# CurrentSense.net
KiCad netlist of a schematic drawn in Altium Designer
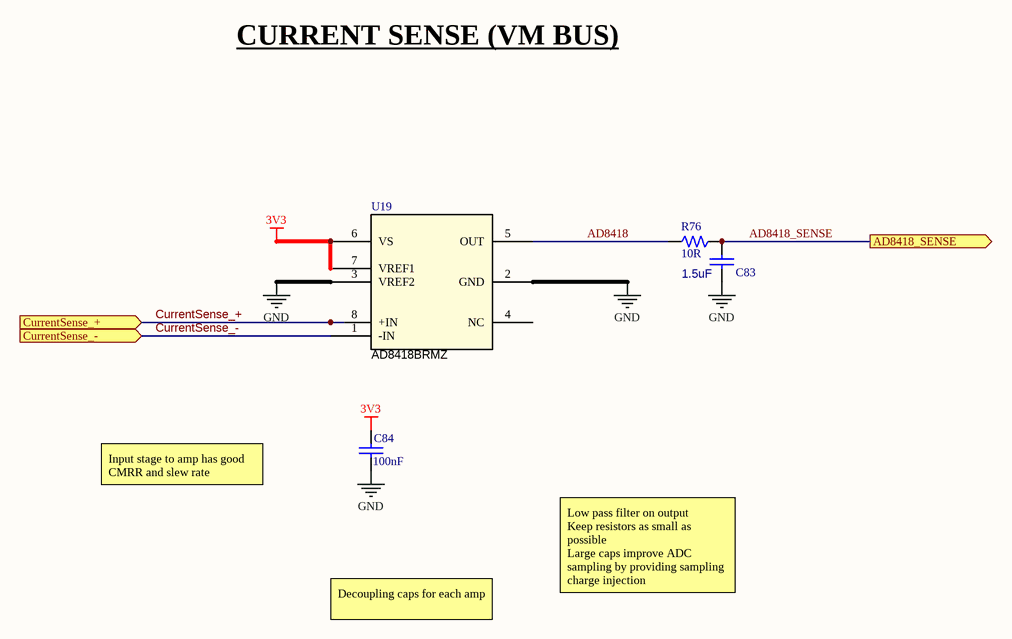
[diagram p0: CurrentSense.SchDoc]

(export (version "E")
  (design (tool "Eeschema 10.0.6"))
  (components
    (comp (ref "C83")
      (value "Capacitor")
      (footprint "CAP0402")
      (description "CAP CER 1.5UF 35V X5R 0402")
      (fields (field (name "CAPACITANCE") "1.5uF"))
      (libsource (lib "") (part "Capacitor_1"))
    )
    (comp (ref "C84")
      (value "Capacitor")
      (footprint "CAP0402")
      (fields
        (field (name "MANUFACTURER") "TDK")
        (field (name "MANUFACTURER PART NUMBER") "CGA2B3X7R1H104K050BB")
        (field (name "CAPACITANCE") "100nF")
        (field (name "TOLERANCE") "10%")
      )
      (libsource (lib "BPL-ShematicLibrary") (part "Capacitor"))
    )
    (comp (ref "R76")
      (value "Resistor")
      (footprint "RES0402")
      (fields (field (name "RESISTANCE") "10R") (field (name "TOLERANCE") "1%"))
      (libsource (lib "BPL-ShematicLibrary") (part "Resistor"))
    )
    (comp (ref "U19")
      (value "Current Sense")
      (footprint "AD8418BRMZ")
      (description "Current Sense Amplifier")
      (fields
        (field (name "MANUFACTURER") "Analog Devices Inc")
        (field (name "MANUFACTURER PART NUMBER") "AD8418BRMZ")
      )
      (libsource (lib "BPL-ShematicLibrary") (part "AD8418BRMZ"))
    )
  )
  (nets
    (net (code "1") (name "/AD8418") (class "Default")
      (node (ref "R76") (pin "2") (pinfunction "2_2") (pintype "passive"))
      (node (ref "U19") (pin "5") (pinfunction "OUT_5") (pintype "passive"))
    )
    (net (code "2") (name "/AD8418_SENSE") (class "Default")
      (node (ref "C83") (pin "1") (pinfunction "1_1") (pintype "passive"))
      (node (ref "R76") (pin "1") (pinfunction "1_1") (pintype "passive"))
    )
    (net (code "3") (name "/CurrentSense_+") (class "Default")
      (node (ref "U19") (pin "8") (pinfunction "+IN_8") (pintype "passive"))
    )
    (net (code "4") (name "/CurrentSense_-") (class "Default")
      (node (ref "U19") (pin "1") (pinfunction "-IN_1") (pintype "passive"))
    )
    (net (code "5") (name "3V3") (class "Default")
      (node (ref "C84") (pin "1") (pinfunction "1_1") (pintype "passive"))
      (node (ref "U19") (pin "6") (pinfunction "VS_6") (pintype "passive"))
      (node (ref "U19") (pin "7") (pinfunction "VREF1_7") (pintype "passive"))
    )
    (net (code "6") (name "GND") (class "Default")
      (node (ref "C83") (pin "2") (pinfunction "2_2") (pintype "passive"))
      (node (ref "C84") (pin "2") (pinfunction "2_2") (pintype "passive"))
      (node (ref "U19") (pin "2") (pinfunction "GND_2") (pintype "passive"))
      (node (ref "U19") (pin "3") (pinfunction "VREF2_3") (pintype "passive"))
    )
    (net (code "7") (name "unconnected-(U19-NC-Pad4)") (class "Default")
      (node (ref "U19") (pin "4") (pinfunction "NC_4") (pintype "passive"))
    )
  )
)
